# EM2050.net
KiCad netlist of a schematic drawn in Altium Designer
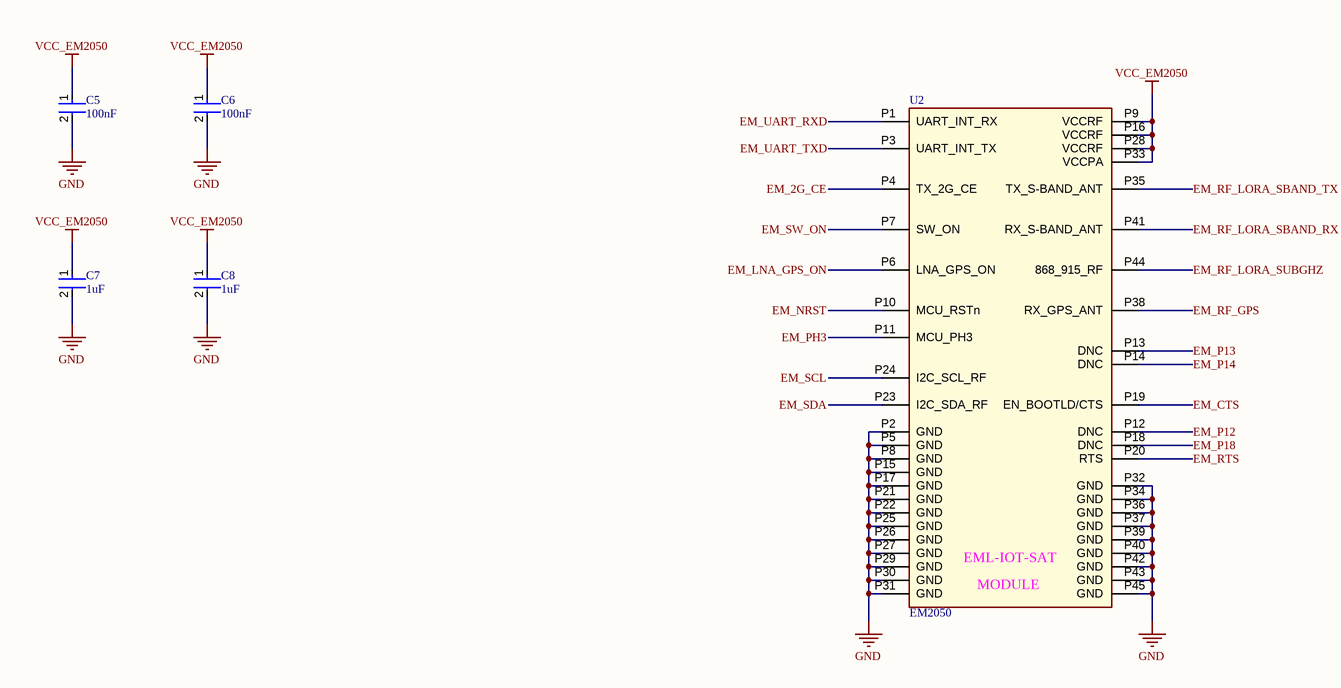
[diagram p0: EM2050.SchDoc]

(export (version "E")
  (design (tool "Eeschema 10.0.6"))
  (components
    (comp (ref "C5")
      (value "0402ZD104KAT2A")
      (footprint "FP-0402-L_1_0_1-W_0_5_0_1-IPC_C")
      (description "General Purpose Ceramic Capacitor, 0402, 100nF, 10%, X5R, 15%, 10V")
      (fields
        (field (name "VOLTAGE") "10V")
        (field (name "TOLERANCE") "10%")
        (field (name "CAPACITANCE") "100nF")
      )
      (libsource (lib "Altium Content Vault") (part "b4654b650e69147ec39a6b967a45e02"))
    )
    (comp (ref "C6")
      (value "0402ZD104KAT2A")
      (footprint "FP-0402-L_1_0_1-W_0_5_0_1-IPC_C")
      (description "General Purpose Ceramic Capacitor, 0402, 100nF, 10%, X5R, 15%, 10V")
      (fields
        (field (name "VOLTAGE") "10V")
        (field (name "TOLERANCE") "10%")
        (field (name "CAPACITANCE") "100nF")
      )
      (libsource (lib "Altium Content Vault") (part "b4654b650e69147ec39a6b967a45e02"))
    )
    (comp (ref "C7")
      (value "EMK105BJ105KV-F")
      (footprint "FP-0402-L_1_0_0_05-W_0_5-IPC_A")
      (description "None")
      (fields (field (name "TOLERANCE") "10%") (field (name "CAPACITANCE") "1uF"))
      (libsource (lib "Altium Content Vault") (part "b4654b650e69147ec39a6b967a45e02"))
    )
    (comp (ref "C8")
      (value "EMK105BJ105KV-F")
      (footprint "FP-0402-L_1_0_0_05-W_0_5-IPC_A")
      (description "None")
      (fields (field (name "TOLERANCE") "10%") (field (name "CAPACITANCE") "1uF"))
      (libsource (lib "Altium Content Vault") (part "b4654b650e69147ec39a6b967a45e02"))
    )
    (comp (ref "U2")
      (value "EM2050")
      (footprint "EM2050")
      (description "Echostar Mobile IOT SAT Module - Basic version")
      (fields (field (name "MANUFACTURER") "Echostar Mobile Ltd") (field (name "Comment") "IOT SAT module"))
      (libsource (lib "EchoStar") (part "EM2050"))
    )
  )
  (nets
    (net (code "1") (name "/EM_2G_CE") (class "Default")
      (node (ref "U2") (pin "P4") (pinfunction "TX_2G_CE_P4") (pintype "passive"))
    )
    (net (code "2") (name "/EM_CTS") (class "Default")
      (node (ref "U2") (pin "P19") (pinfunction "EN_BOOTLD/CTS_P19") (pintype "passive"))
    )
    (net (code "3") (name "/EM_LNA_GPS_ON") (class "Default")
      (node (ref "U2") (pin "P6") (pinfunction "LNA_GPS_ON_P6") (pintype "passive"))
    )
    (net (code "4") (name "/EM_NRST") (class "Default")
      (node (ref "U2") (pin "P10") (pinfunction "MCU_RSTn_P10") (pintype "passive"))
    )
    (net (code "5") (name "/EM_P12") (class "Default")
      (node (ref "U2") (pin "P12") (pinfunction "DNC_P12") (pintype "passive"))
    )
    (net (code "6") (name "/EM_P13") (class "Default")
      (node (ref "U2") (pin "P13") (pinfunction "DNC_P13") (pintype "passive"))
    )
    (net (code "7") (name "/EM_P14") (class "Default")
      (node (ref "U2") (pin "P14") (pinfunction "DNC_P14") (pintype "passive"))
    )
    (net (code "8") (name "/EM_P18") (class "Default")
      (node (ref "U2") (pin "P18") (pinfunction "DNC_P18") (pintype "passive"))
    )
    (net (code "9") (name "/EM_PH3") (class "Default")
      (node (ref "U2") (pin "P11") (pinfunction "MCU_PH3_P11") (pintype "passive"))
    )
    (net (code "10") (name "/EM_RF_GPS") (class "Default")
      (node (ref "U2") (pin "P38") (pinfunction "RX_GPS_ANT_P38") (pintype "passive"))
    )
    (net (code "11") (name "/EM_RF_LORA_SBAND_RX") (class "Default")
      (node (ref "U2") (pin "P41") (pinfunction "RX_S-BAND_ANT_P41") (pintype "passive"))
    )
    (net (code "12") (name "/EM_RF_LORA_SBAND_TX") (class "Default")
      (node (ref "U2") (pin "P35") (pinfunction "TX_S-BAND_ANT_P35") (pintype "passive"))
    )
    (net (code "13") (name "/EM_RF_LORA_SUBGHZ") (class "Default")
      (node (ref "U2") (pin "P44") (pinfunction "868_915_RF_P44") (pintype "passive"))
    )
    (net (code "14") (name "/EM_RTS") (class "Default")
      (node (ref "U2") (pin "P20") (pinfunction "RTS_P20") (pintype "passive"))
    )
    (net (code "15") (name "/EM_SCL") (class "Default")
      (node (ref "U2") (pin "P24") (pinfunction "I2C_SCL_RF_P24") (pintype "passive"))
    )
    (net (code "16") (name "/EM_SDA") (class "Default")
      (node (ref "U2") (pin "P23") (pinfunction "I2C_SDA_RF_P23") (pintype "passive"))
    )
    (net (code "17") (name "/EM_SW_ON") (class "Default")
      (node (ref "U2") (pin "P7") (pinfunction "SW_ON_P7") (pintype "passive"))
    )
    (net (code "18") (name "/EM_UART_RXD") (class "Default")
      (node (ref "U2") (pin "P1") (pinfunction "UART_INT_RX_P1") (pintype "passive"))
    )
    (net (code "19") (name "/EM_UART_TXD") (class "Default")
      (node (ref "U2") (pin "P3") (pinfunction "UART_INT_TX_P3") (pintype "passive"))
    )
    (net (code "20") (name "GND") (class "Default")
      (node (ref "C5") (pin "2") (pinfunction "2_2") (pintype "passive"))
      (node (ref "C6") (pin "2") (pinfunction "2_2") (pintype "passive"))
      (node (ref "C7") (pin "2") (pinfunction "2_2") (pintype "passive"))
      (node (ref "C8") (pin "2") (pinfunction "2_2") (pintype "passive"))
      (node (ref "U2") (pin "P15") (pinfunction "GND_P15") (pintype "passive"))
      (node (ref "U2") (pin "P17") (pinfunction "GND_P17") (pintype "passive"))
      (node (ref "U2") (pin "P2") (pinfunction "GND_P2") (pintype "passive"))
      (node (ref "U2") (pin "P21") (pinfunction "GND_P21") (pintype "passive"))
      (node (ref "U2") (pin "P22") (pinfunction "GND_P22") (pintype "passive"))
      (node (ref "U2") (pin "P25") (pinfunction "GND_P25") (pintype "passive"))
      (node (ref "U2") (pin "P26") (pinfunction "GND_P26") (pintype "passive"))
      (node (ref "U2") (pin "P27") (pinfunction "GND_P27") (pintype "passive"))
      (node (ref "U2") (pin "P29") (pinfunction "GND_P29") (pintype "passive"))
      (node (ref "U2") (pin "P30") (pinfunction "GND_P30") (pintype "passive"))
      (node (ref "U2") (pin "P31") (pinfunction "GND_P31") (pintype "passive"))
      (node (ref "U2") (pin "P32") (pinfunction "GND_P32") (pintype "passive"))
      (node (ref "U2") (pin "P34") (pinfunction "GND_P34") (pintype "passive"))
      (node (ref "U2") (pin "P36") (pinfunction "GND_P36") (pintype "passive"))
      (node (ref "U2") (pin "P37") (pinfunction "GND_P37") (pintype "passive"))
      (node (ref "U2") (pin "P39") (pinfunction "GND_P39") (pintype "passive"))
      (node (ref "U2") (pin "P40") (pinfunction "GND_P40") (pintype "passive"))
      (node (ref "U2") (pin "P42") (pinfunction "GND_P42") (pintype "passive"))
      (node (ref "U2") (pin "P43") (pinfunction "GND_P43") (pintype "passive"))
      (node (ref "U2") (pin "P45") (pinfunction "GND_P45") (pintype "passive"))
      (node (ref "U2") (pin "P5") (pinfunction "GND_P5") (pintype "passive"))
      (node (ref "U2") (pin "P8") (pinfunction "GND_P8") (pintype "passive"))
    )
    (net (code "21") (name "VCC_EM2050") (class "Default")
      (node (ref "C5") (pin "1") (pinfunction "1_1") (pintype "passive"))
      (node (ref "C6") (pin "1") (pinfunction "1_1") (pintype "passive"))
      (node (ref "C7") (pin "1") (pinfunction "1_1") (pintype "passive"))
      (node (ref "C8") (pin "1") (pinfunction "1_1") (pintype "passive"))
      (node (ref "U2") (pin "P16") (pinfunction "VCCRF_P16") (pintype "passive"))
      (node (ref "U2") (pin "P28") (pinfunction "VCCRF_P28") (pintype "passive"))
      (node (ref "U2") (pin "P33") (pinfunction "VCCPA_P33") (pintype "passive"))
      (node (ref "U2") (pin "P9") (pinfunction "VCCRF_P9") (pintype "passive"))
    )
  )
)
